# PSU_Schematic.net
KiCad netlist of a schematic drawn in Altium Designer
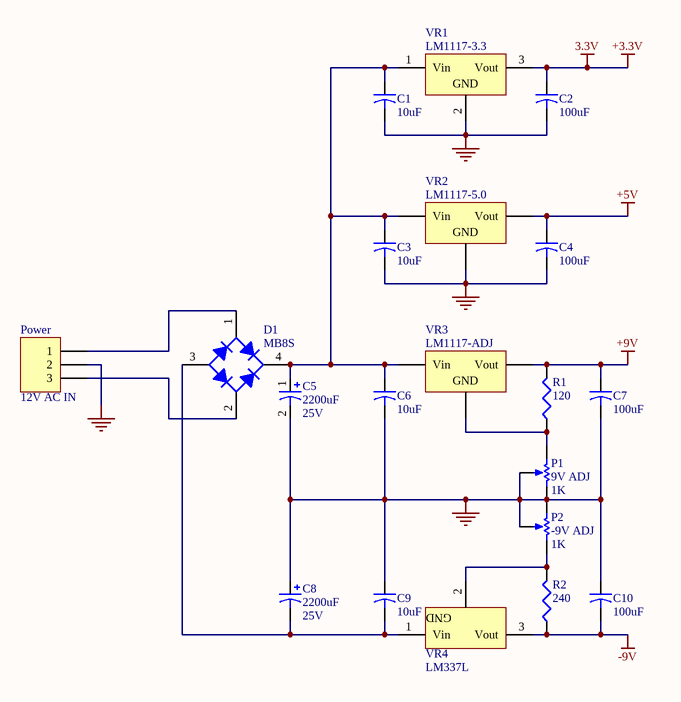
[diagram p0: PSU.Schematic.SchDoc]

(export (version "E")
  (design (tool "Eeschema 10.0.6"))
  (components
    (comp (ref "C1")
      (value "10uF")
      (footprint "CAPC1608N")
      (description "Capacitor")
      (fields (field (name "PUBLISHER") "Altium Limited"))
      (libsource (lib "Miscellaneous Devices") (part "Cap2"))
    )
    (comp (ref "C2")
      (value "100uF")
      (footprint "CAPC1608N")
      (description "Capacitor")
      (fields (field (name "PUBLISHER") "Altium Limited"))
      (libsource (lib "Miscellaneous Devices") (part "Cap2"))
    )
    (comp (ref "C3")
      (value "10uF")
      (footprint "CAPC1608N")
      (description "Capacitor")
      (fields (field (name "PUBLISHER") "Altium Limited"))
      (libsource (lib "Miscellaneous Devices") (part "Cap2"))
    )
    (comp (ref "C4")
      (value "100uF")
      (footprint "CAPC1608N")
      (description "Capacitor")
      (fields (field (name "PUBLISHER") "Altium Limited"))
      (libsource (lib "Miscellaneous Devices") (part "Cap2"))
    )
    (comp (ref "C5")
      (value "2200uF")
      (footprint "Condo electro 13")
      (description "Polarized Capacitor (Radial)")
      (fields (field (name "ALTIUM_VALUE") "25V") (field (name "PUBLISHER") "Altium Limited"))
      (libsource (lib "") (part "Cap Pol1_1"))
    )
    (comp (ref "C6")
      (value "10uF")
      (footprint "CAPC1608N")
      (description "Capacitor")
      (fields (field (name "PUBLISHER") "Altium Limited"))
      (libsource (lib "Miscellaneous Devices") (part "Cap2"))
    )
    (comp (ref "C7")
      (value "100uF")
      (footprint "CAPC1608N")
      (description "Capacitor")
      (fields (field (name "PUBLISHER") "Altium Limited"))
      (libsource (lib "Miscellaneous Devices") (part "Cap2"))
    )
    (comp (ref "C8")
      (value "2200uF")
      (footprint "Condo electro 13")
      (description "Polarized Capacitor (Radial)")
      (fields (field (name "ALTIUM_VALUE") "25V") (field (name "PUBLISHER") "Altium Limited"))
      (libsource (lib "Miscellaneous Devices") (part "Cap Pol1"))
    )
    (comp (ref "C9")
      (value "10uF")
      (footprint "CAPC1608N")
      (description "Capacitor")
      (fields (field (name "PUBLISHER") "Altium Limited"))
      (libsource (lib "Miscellaneous Devices") (part "Cap2"))
    )
    (comp (ref "C10")
      (value "100uF")
      (footprint "CAPC1608N")
      (description "Capacitor")
      (fields (field (name "PUBLISHER") "Altium Limited"))
      (libsource (lib "Miscellaneous Devices") (part "Cap2"))
    )
    (comp (ref "D1")
      (value "MB8S")
      (footprint "MB8S")
      (description "Full Wave Diode Bridge")
      (fields (field (name "PUBLISHER") "Altium Limited"))
      (libsource (lib "Miscellaneous Devices") (part "Bridge1"))
    )
    (comp (ref "P1")
      (value "9V ADJ")
      (footprint "BOURNS Trim pot")
      (description "Potentiometer")
      (fields (field (name "ALTIUM_VALUE") "1K") (field (name "PUBLISHER") "Altium Limited"))
      (libsource (lib "Miscellaneous Devices") (part "RPot"))
    )
    (comp (ref "P2")
      (value "-9V ADJ")
      (footprint "BOURNS Trim pot")
      (description "Potentiometer")
      (fields (field (name "ALTIUM_VALUE") "1K") (field (name "PUBLISHER") "Altium Limited"))
      (libsource (lib "Miscellaneous Devices") (part "RPot"))
    )
    (comp (ref "Power")
      (value "12V AC IN")
      (footprint "Header 3")
      (description "Header, 3-Pin")
      (fields (field (name "PUBLISHER") "Altium Limited"))
      (libsource (lib "Miscellaneous Connectors") (part "Header 3"))
    )
    (comp (ref "R1")
      (value "120")
      (footprint "CAPC1608N")
      (description "Resistor")
      (fields (field (name "PUBLISHER") "Altium Limited"))
      (libsource (lib "Miscellaneous Devices") (part "Res3"))
    )
    (comp (ref "R2")
      (value "240")
      (footprint "CAPC1608N")
      (description "Resistor")
      (fields (field (name "PUBLISHER") "Altium Limited"))
      (libsource (lib "Miscellaneous Devices") (part "Res3"))
    )
    (comp (ref "VR1")
      (value "LM1117-3.3")
      (footprint "LM1117-SOT")
      (description "Voltage Regulator")
      (fields (field (name "PUBLISHER") "Altium Limited"))
      (libsource (lib "") (part "Volt Reg_2"))
    )
    (comp (ref "VR2")
      (value "LM1117-5.0")
      (footprint "LM1117-SOT")
      (description "Voltage Regulator")
      (fields (field (name "PUBLISHER") "Altium Limited"))
      (libsource (lib "Miscellaneous Devices") (part "Volt Reg"))
    )
    (comp (ref "VR3")
      (value "LM1117-ADJ")
      (footprint "LM1117-SOT")
      (description "Voltage Regulator")
      (fields (field (name "PUBLISHER") "Altium Limited"))
      (libsource (lib "") (part "Volt Reg_1"))
    )
    (comp (ref "VR4")
      (value "LM337L")
      (footprint "LM337L")
      (description "Voltage Regulator")
      (fields (field (name "PUBLISHER") "Altium Limited"))
      (libsource (lib "") (part "Volt Reg_3"))
    )
  )
  (nets
    (net (code "1") (name "+3.3V") (class "Default")
      (node (ref "C2") (pin "1") (pinfunction "1_1") (pintype "passive"))
      (node (ref "VR1") (pin "3") (pinfunction "Vout_3") (pintype "passive"))
    )
    (net (code "2") (name "+5V") (class "Default")
      (node (ref "C4") (pin "1") (pinfunction "1_1") (pintype "passive"))
      (node (ref "VR2") (pin "3") (pinfunction "Vout_3") (pintype "passive"))
    )
    (net (code "3") (name "+9V") (class "Default")
      (node (ref "C7") (pin "1") (pinfunction "1_1") (pintype "passive"))
      (node (ref "R1") (pin "2") (pinfunction "2_2") (pintype "passive"))
      (node (ref "VR3") (pin "3") (pinfunction "Vout_3") (pintype "passive"))
    )
    (net (code "4") (name "-9V") (class "Default")
      (node (ref "C10") (pin "2") (pinfunction "2_2") (pintype "passive"))
      (node (ref "R2") (pin "1") (pinfunction "1_1") (pintype "passive"))
      (node (ref "VR4") (pin "3") (pinfunction "Vout_3") (pintype "passive"))
    )
    (net (code "5") (name "GND") (class "Default")
      (node (ref "C1") (pin "2") (pinfunction "2_2") (pintype "passive"))
      (node (ref "C10") (pin "1") (pinfunction "1_1") (pintype "passive"))
      (node (ref "C2") (pin "2") (pinfunction "2_2") (pintype "passive"))
      (node (ref "C3") (pin "2") (pinfunction "2_2") (pintype "passive"))
      (node (ref "C4") (pin "2") (pinfunction "2_2") (pintype "passive"))
      (node (ref "C5") (pin "2") (pinfunction "2_2") (pintype "passive"))
      (node (ref "C6") (pin "2") (pinfunction "2_2") (pintype "passive"))
      (node (ref "C7") (pin "2") (pinfunction "2_2") (pintype "passive"))
      (node (ref "C8") (pin "1") (pinfunction "1_1") (pintype "passive"))
      (node (ref "C9") (pin "1") (pinfunction "1_1") (pintype "passive"))
      (node (ref "P1") (pin "1") (pinfunction "TOP_1") (pintype "passive"))
      (node (ref "P1") (pin "3") (pinfunction "TAP_3") (pintype "passive"))
      (node (ref "P2") (pin "2") (pinfunction "BOT_2") (pintype "passive"))
      (node (ref "P2") (pin "3") (pinfunction "TAP_3") (pintype "passive"))
      (node (ref "Power") (pin "2") (pinfunction "2_2") (pintype "passive"))
      (node (ref "VR1") (pin "2") (pinfunction "GND_2") (pintype "passive"))
      (node (ref "VR2") (pin "2") (pinfunction "GND_2") (pintype "passive"))
    )
    (net (code "6") (name "Net-(D1-A)") (class "Default")
      (node (ref "C8") (pin "2") (pinfunction "2_2") (pintype "passive"))
      (node (ref "C9") (pin "2") (pinfunction "2_2") (pintype "passive"))
      (node (ref "D1") (pin "3") (pinfunction "A_3") (pintype "passive"))
      (node (ref "VR4") (pin "1") (pinfunction "Vin_1") (pintype "passive"))
    )
    (net (code "7") (name "Net-(D1-C-Pad1)") (class "Default")
      (node (ref "D1") (pin "1") (pinfunction "C_1") (pintype "passive"))
      (node (ref "Power") (pin "1") (pinfunction "1_1") (pintype "passive"))
    )
    (net (code "8") (name "Net-(D1-C-Pad2)") (class "Default")
      (node (ref "D1") (pin "2") (pinfunction "C_2") (pintype "passive"))
      (node (ref "Power") (pin "3") (pinfunction "3_3") (pintype "passive"))
    )
    (net (code "9") (name "Net-(D1-K)") (class "Default")
      (node (ref "C1") (pin "1") (pinfunction "1_1") (pintype "passive"))
      (node (ref "C3") (pin "1") (pinfunction "1_1") (pintype "passive"))
      (node (ref "C5") (pin "1") (pinfunction "1_1") (pintype "passive"))
      (node (ref "C6") (pin "1") (pinfunction "1_1") (pintype "passive"))
      (node (ref "D1") (pin "4") (pinfunction "K_4") (pintype "passive"))
      (node (ref "VR1") (pin "1") (pinfunction "Vin_1") (pintype "passive"))
      (node (ref "VR2") (pin "1") (pinfunction "Vin_1") (pintype "passive"))
      (node (ref "VR3") (pin "1") (pinfunction "Vin_1") (pintype "passive"))
    )
    (net (code "10") (name "Net-(P1-BOT)") (class "Default")
      (node (ref "P1") (pin "2") (pinfunction "BOT_2") (pintype "passive"))
      (node (ref "R1") (pin "1") (pinfunction "1_1") (pintype "passive"))
      (node (ref "VR3") (pin "2") (pinfunction "ADJ_2") (pintype "passive"))
    )
    (net (code "11") (name "Net-(P2-TOP)") (class "Default")
      (node (ref "P2") (pin "1") (pinfunction "TOP_1") (pintype "passive"))
      (node (ref "R2") (pin "2") (pinfunction "2_2") (pintype "passive"))
      (node (ref "VR4") (pin "2") (pinfunction "ADJ_2") (pintype "passive"))
    )
  )
)
